# Zaliczeniowy.net
KiCad netlist of a schematic drawn in EAGLE
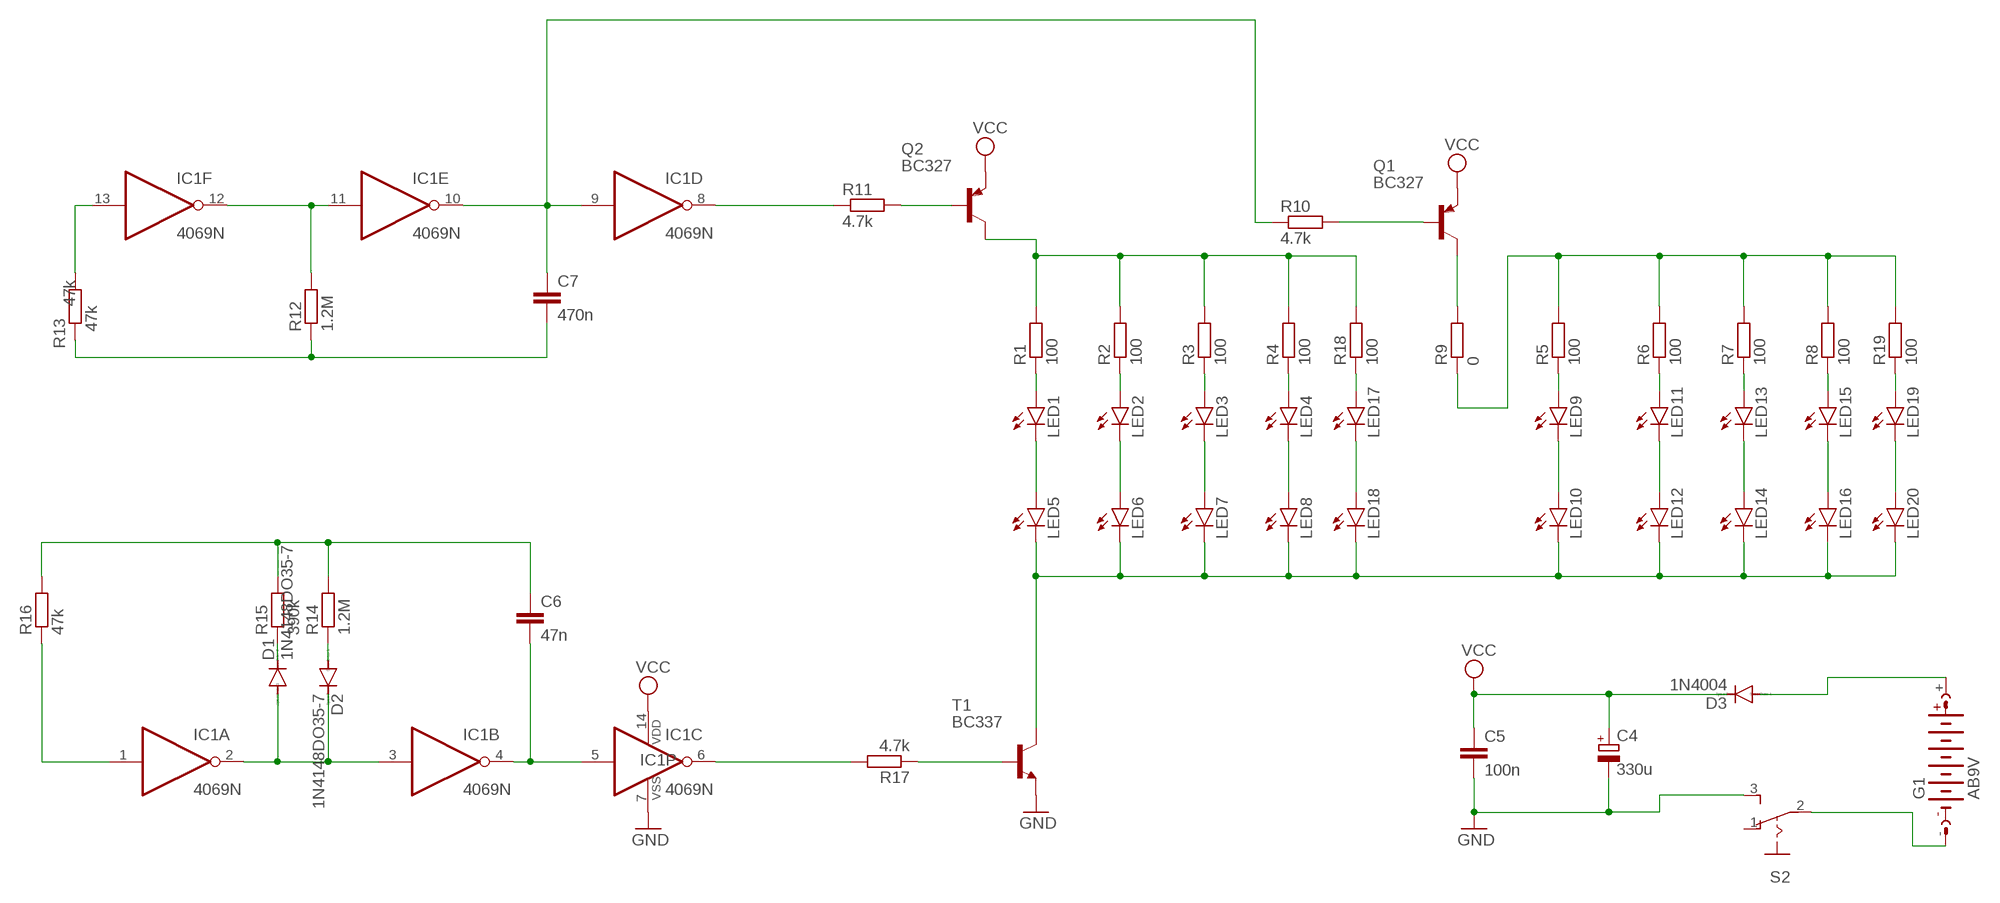
[diagram p0: schematic, sheet 1]

(export (version "E")
  (design (tool "Eeschema 10.0.6"))
  (components
    (comp (ref "C4")
      (value "330u")
      (footprint "eagle-import:E2-5")
      (libsource (lib "eagle-import") (part "CPOL-EUE2-5"))
    )
    (comp (ref "C5")
      (value "100n")
      (footprint "eagle-import:C025-024X044")
      (libsource (lib "eagle-import") (part "C-EU025-024X044"))
    )
    (comp (ref "C6")
      (value "47n")
      (footprint "eagle-import:C025-024X044")
      (libsource (lib "eagle-import") (part "C-EU025-024X044"))
    )
    (comp (ref "C7")
      (value "470n")
      (footprint "eagle-import:C025-024X044")
      (libsource (lib "eagle-import") (part "C-EU025-024X044"))
    )
    (comp (ref "D1")
      (value "1N4148DO35-7")
      (footprint "eagle-import:DO35-7")
      (libsource (lib "eagle-import") (part "1N4148DO35-7"))
    )
    (comp (ref "D2")
      (value "1N4148DO35-7")
      (footprint "eagle-import:DO35-7")
      (libsource (lib "eagle-import") (part "1N4148DO35-7"))
    )
    (comp (ref "D3")
      (value "1N4004")
      (footprint "eagle-import:DO41-10")
      (libsource (lib "eagle-import") (part "1N4004"))
    )
    (comp (ref "G1")
      (value "AB9V")
      (footprint "eagle-import:AB9V")
      (libsource (lib "eagle-import") (part "AB9V"))
    )
    (comp (ref "IC1")
      (value "4069N")
      (footprint "eagle-import:DIL14")
      (libsource (lib "eagle-import") (part "4069N"))
    )
    (comp (ref "LED1")
      (value "LED5MM")
      (footprint "eagle-import:LED5MM")
      (libsource (lib "eagle-import") (part "LED5MM"))
    )
    (comp (ref "LED2")
      (value "LED5MM")
      (footprint "eagle-import:LED5MM")
      (libsource (lib "eagle-import") (part "LED5MM"))
    )
    (comp (ref "LED3")
      (value "LED5MM")
      (footprint "eagle-import:LED5MM")
      (libsource (lib "eagle-import") (part "LED5MM"))
    )
    (comp (ref "LED4")
      (value "LED5MM")
      (footprint "eagle-import:LED5MM")
      (libsource (lib "eagle-import") (part "LED5MM"))
    )
    (comp (ref "LED5")
      (value "LED5MM")
      (footprint "eagle-import:LED5MM")
      (libsource (lib "eagle-import") (part "LED5MM"))
    )
    (comp (ref "LED6")
      (value "LED5MM")
      (footprint "eagle-import:LED5MM")
      (libsource (lib "eagle-import") (part "LED5MM"))
    )
    (comp (ref "LED7")
      (value "LED5MM")
      (footprint "eagle-import:LED5MM")
      (libsource (lib "eagle-import") (part "LED5MM"))
    )
    (comp (ref "LED8")
      (value "LED5MM")
      (footprint "eagle-import:LED5MM")
      (libsource (lib "eagle-import") (part "LED5MM"))
    )
    (comp (ref "LED9")
      (value "LED5MM")
      (footprint "eagle-import:LED5MM")
      (libsource (lib "eagle-import") (part "LED5MM"))
    )
    (comp (ref "LED10")
      (value "LED5MM")
      (footprint "eagle-import:LED5MM")
      (libsource (lib "eagle-import") (part "LED5MM"))
    )
    (comp (ref "LED11")
      (value "LED5MM")
      (footprint "eagle-import:LED5MM")
      (libsource (lib "eagle-import") (part "LED5MM"))
    )
    (comp (ref "LED12")
      (value "LED5MM")
      (footprint "eagle-import:LED5MM")
      (libsource (lib "eagle-import") (part "LED5MM"))
    )
    (comp (ref "LED13")
      (value "LED5MM")
      (footprint "eagle-import:LED5MM")
      (libsource (lib "eagle-import") (part "LED5MM"))
    )
    (comp (ref "LED14")
      (value "LED5MM")
      (footprint "eagle-import:LED5MM")
      (libsource (lib "eagle-import") (part "LED5MM"))
    )
    (comp (ref "LED15")
      (value "LED5MM")
      (footprint "eagle-import:LED5MM")
      (libsource (lib "eagle-import") (part "LED5MM"))
    )
    (comp (ref "LED16")
      (value "LED5MM")
      (footprint "eagle-import:LED5MM")
      (libsource (lib "eagle-import") (part "LED5MM"))
    )
    (comp (ref "LED17")
      (value "LED5MM")
      (footprint "eagle-import:LED5MM")
      (libsource (lib "eagle-import") (part "LED5MM"))
    )
    (comp (ref "LED18")
      (value "LED5MM")
      (footprint "eagle-import:LED5MM")
      (libsource (lib "eagle-import") (part "LED5MM"))
    )
    (comp (ref "LED19")
      (value "LED5MM")
      (footprint "eagle-import:LED5MM")
      (libsource (lib "eagle-import") (part "LED5MM"))
    )
    (comp (ref "LED20")
      (value "LED5MM")
      (footprint "eagle-import:LED5MM")
      (libsource (lib "eagle-import") (part "LED5MM"))
    )
    (comp (ref "Q1")
      (value "BC327")
      (footprint "eagle-import:TO92")
      (libsource (lib "eagle-import") (part "BC327"))
    )
    (comp (ref "Q2")
      (value "BC327")
      (footprint "eagle-import:TO92")
      (libsource (lib "eagle-import") (part "BC327"))
    )
    (comp (ref "R1")
      (value "100")
      (footprint "eagle-import:0207_7")
      (libsource (lib "eagle-import") (part "R-EU_0207/7"))
    )
    (comp (ref "R2")
      (value "100")
      (footprint "eagle-import:0207_7")
      (libsource (lib "eagle-import") (part "R-EU_0207/7"))
    )
    (comp (ref "R3")
      (value "100")
      (footprint "eagle-import:0207_7")
      (libsource (lib "eagle-import") (part "R-EU_0207/7"))
    )
    (comp (ref "R4")
      (value "100")
      (footprint "eagle-import:0207_7")
      (libsource (lib "eagle-import") (part "R-EU_0207/7"))
    )
    (comp (ref "R5")
      (value "100")
      (footprint "eagle-import:0207_7")
      (libsource (lib "eagle-import") (part "R-EU_0207/7"))
    )
    (comp (ref "R6")
      (value "100")
      (footprint "eagle-import:0207_7")
      (libsource (lib "eagle-import") (part "R-EU_0207/7"))
    )
    (comp (ref "R7")
      (value "100")
      (footprint "eagle-import:0207_7")
      (libsource (lib "eagle-import") (part "R-EU_0207/7"))
    )
    (comp (ref "R8")
      (value "100")
      (footprint "eagle-import:0207_7")
      (libsource (lib "eagle-import") (part "R-EU_0207/7"))
    )
    (comp (ref "R9")
      (value "0")
      (footprint "eagle-import:0207_7")
      (libsource (lib "eagle-import") (part "R-EU_0207/7"))
    )
    (comp (ref "R10")
      (value "4.7k")
      (footprint "eagle-import:0207_7")
      (libsource (lib "eagle-import") (part "R-EU_0207/7"))
    )
    (comp (ref "R11")
      (value "4.7k")
      (footprint "eagle-import:0207_7")
      (libsource (lib "eagle-import") (part "R-EU_0207/7"))
    )
    (comp (ref "R12")
      (value "1.2M")
      (footprint "eagle-import:0207_7")
      (libsource (lib "eagle-import") (part "R-EU_0207/7"))
    )
    (comp (ref "R13")
      (value "47k")
      (footprint "eagle-import:0207_7")
      (fields (field (name "POPULARITY") "46") (field (name "POPULARITY_1") "47k"))
      (libsource (lib "eagle-import") (part "R-EU_0207/7"))
    )
    (comp (ref "R14")
      (value "1.2M")
      (footprint "eagle-import:0207_7")
      (libsource (lib "eagle-import") (part "R-EU_0207/7"))
    )
    (comp (ref "R15")
      (value "390k")
      (footprint "eagle-import:0207_7")
      (libsource (lib "eagle-import") (part "R-EU_0207/7"))
    )
    (comp (ref "R16")
      (value "47k")
      (footprint "eagle-import:0207_7")
      (libsource (lib "eagle-import") (part "R-EU_0207/7"))
    )
    (comp (ref "R17")
      (value "4.7k")
      (footprint "eagle-import:0207_7")
      (libsource (lib "eagle-import") (part "R-EU_0207/7"))
    )
    (comp (ref "R18")
      (value "100")
      (footprint "eagle-import:0207_7")
      (libsource (lib "eagle-import") (part "R-EU_0207/7"))
    )
    (comp (ref "R19")
      (value "100")
      (footprint "eagle-import:0207_7")
      (libsource (lib "eagle-import") (part "R-EU_0207/7"))
    )
    (comp (ref "S2")
      (value "255SB")
      (footprint "eagle-import:255SB")
      (libsource (lib "eagle-import") (part "255SB"))
    )
    (comp (ref "T1")
      (value "BC337")
      (footprint "eagle-import:TO92-CBE")
      (libsource (lib "eagle-import") (part "-NPN-TO92-CBEBC337-16"))
    )
  )
  (nets
    (net (code "1") (name "GND") (class "Default")
      (node (ref "C4") (pin "-") (pinfunction "-_-") (pintype "passive"))
      (node (ref "C5") (pin "2") (pinfunction "2_2") (pintype "passive"))
      (node (ref "IC1") (pin "7") (pinfunction "VSS_7") (pintype "power_in"))
      (node (ref "S2") (pin "3") (pinfunction "S_3") (pintype "passive"))
      (node (ref "T1") (pin "E") (pinfunction "E_E") (pintype "passive"))
    )
    (net (code "2") (name "Net-(C6-Pad1)") (class "Default")
      (node (ref "C6") (pin "1") (pinfunction "1_1") (pintype "passive"))
      (node (ref "R14") (pin "2") (pinfunction "2_2") (pintype "passive"))
      (node (ref "R15") (pin "2") (pinfunction "2_2") (pintype "passive"))
      (node (ref "R16") (pin "2") (pinfunction "2_2") (pintype "passive"))
    )
    (net (code "3") (name "Net-(C7-Pad2)") (class "Default")
      (node (ref "C7") (pin "2") (pinfunction "2_2") (pintype "passive"))
      (node (ref "R12") (pin "1") (pinfunction "1_1") (pintype "passive"))
      (node (ref "R13") (pin "1") (pinfunction "1_1") (pintype "passive"))
    )
    (net (code "4") (name "Net-(D1-PadC)") (class "Default")
      (node (ref "D1") (pin "C") (pinfunction "C_C") (pintype "passive"))
      (node (ref "R15") (pin "1") (pinfunction "1_1") (pintype "passive"))
    )
    (net (code "5") (name "Net-(D2-PadA)") (class "Default")
      (node (ref "D2") (pin "A") (pinfunction "A_A") (pintype "passive"))
      (node (ref "R14") (pin "1") (pinfunction "1_1") (pintype "passive"))
    )
    (net (code "6") (name "Net-(D3-PadA)") (class "Default")
      (node (ref "D3") (pin "A") (pinfunction "A_A") (pintype "passive"))
      (node (ref "G1") (pin "+") (pinfunction "+_+") (pintype "passive"))
    )
    (net (code "7") (name "Net-(IC1A-I)") (class "Default")
      (node (ref "IC1") (pin "1") (pinfunction "I_1") (pintype "input"))
      (node (ref "R16") (pin "1") (pinfunction "1_1") (pintype "passive"))
    )
    (net (code "8") (name "Net-(IC1A-O)") (class "Default")
      (node (ref "D1") (pin "A") (pinfunction "A_A") (pintype "passive"))
      (node (ref "D2") (pin "C") (pinfunction "C_C") (pintype "passive"))
      (node (ref "IC1") (pin "2") (pinfunction "O_2") (pintype "output"))
      (node (ref "IC1") (pin "3") (pinfunction "I_3") (pintype "input"))
    )
    (net (code "9") (name "Net-(IC1B-O)") (class "Default")
      (node (ref "C6") (pin "2") (pinfunction "2_2") (pintype "passive"))
      (node (ref "IC1") (pin "4") (pinfunction "O_4") (pintype "output"))
      (node (ref "IC1") (pin "5") (pinfunction "I_5") (pintype "input"))
    )
    (net (code "10") (name "Net-(IC1C-O)") (class "Default")
      (node (ref "IC1") (pin "6") (pinfunction "O_6") (pintype "output"))
      (node (ref "R17") (pin "2") (pinfunction "2_2") (pintype "passive"))
    )
    (net (code "11") (name "Net-(IC1D-I)") (class "Default")
      (node (ref "C7") (pin "1") (pinfunction "1_1") (pintype "passive"))
      (node (ref "IC1") (pin "10") (pinfunction "O_10") (pintype "output"))
      (node (ref "IC1") (pin "9") (pinfunction "I_9") (pintype "input"))
      (node (ref "R10") (pin "1") (pinfunction "1_1") (pintype "passive"))
    )
    (net (code "12") (name "Net-(IC1D-O)") (class "Default")
      (node (ref "IC1") (pin "8") (pinfunction "O_8") (pintype "output"))
      (node (ref "R11") (pin "1") (pinfunction "1_1") (pintype "passive"))
    )
    (net (code "13") (name "Net-(IC1E-I)") (class "Default")
      (node (ref "IC1") (pin "11") (pinfunction "I_11") (pintype "input"))
      (node (ref "IC1") (pin "12") (pinfunction "O_12") (pintype "output"))
      (node (ref "R12") (pin "2") (pinfunction "2_2") (pintype "passive"))
    )
    (net (code "14") (name "Net-(IC1F-I)") (class "Default")
      (node (ref "IC1") (pin "13") (pinfunction "I_13") (pintype "input"))
      (node (ref "R13") (pin "2") (pinfunction "2_2") (pintype "passive"))
    )
    (net (code "15") (name "Net-(LED1-C)") (class "Default")
      (node (ref "LED1") (pin "K") (pinfunction "C_K") (pintype "passive"))
      (node (ref "LED5") (pin "A") (pinfunction "A_A") (pintype "passive"))
    )
    (net (code "16") (name "Net-(LED1-PadA)") (class "Default")
      (node (ref "LED1") (pin "A") (pinfunction "A_A") (pintype "passive"))
      (node (ref "R1") (pin "1") (pinfunction "1_1") (pintype "passive"))
    )
    (net (code "17") (name "Net-(LED2-C)") (class "Default")
      (node (ref "LED2") (pin "K") (pinfunction "C_K") (pintype "passive"))
      (node (ref "LED6") (pin "A") (pinfunction "A_A") (pintype "passive"))
    )
    (net (code "18") (name "Net-(LED2-PadA)") (class "Default")
      (node (ref "LED2") (pin "A") (pinfunction "A_A") (pintype "passive"))
      (node (ref "R2") (pin "1") (pinfunction "1_1") (pintype "passive"))
    )
    (net (code "19") (name "Net-(LED3-C)") (class "Default")
      (node (ref "LED3") (pin "K") (pinfunction "C_K") (pintype "passive"))
      (node (ref "LED7") (pin "A") (pinfunction "A_A") (pintype "passive"))
    )
    (net (code "20") (name "Net-(LED3-PadA)") (class "Default")
      (node (ref "LED3") (pin "A") (pinfunction "A_A") (pintype "passive"))
      (node (ref "R3") (pin "1") (pinfunction "1_1") (pintype "passive"))
    )
    (net (code "21") (name "Net-(LED4-C)") (class "Default")
      (node (ref "LED4") (pin "K") (pinfunction "C_K") (pintype "passive"))
      (node (ref "LED8") (pin "A") (pinfunction "A_A") (pintype "passive"))
    )
    (net (code "22") (name "Net-(LED4-PadA)") (class "Default")
      (node (ref "LED4") (pin "A") (pinfunction "A_A") (pintype "passive"))
      (node (ref "R4") (pin "1") (pinfunction "1_1") (pintype "passive"))
    )
    (net (code "23") (name "Net-(LED9-C)") (class "Default")
      (node (ref "LED10") (pin "A") (pinfunction "A_A") (pintype "passive"))
      (node (ref "LED9") (pin "K") (pinfunction "C_K") (pintype "passive"))
    )
    (net (code "24") (name "Net-(LED9-PadA)") (class "Default")
      (node (ref "LED9") (pin "A") (pinfunction "A_A") (pintype "passive"))
      (node (ref "R5") (pin "1") (pinfunction "1_1") (pintype "passive"))
    )
    (net (code "25") (name "Net-(LED10-C)") (class "Default")
      (node (ref "LED10") (pin "K") (pinfunction "C_K") (pintype "passive"))
      (node (ref "LED12") (pin "K") (pinfunction "C_K") (pintype "passive"))
      (node (ref "LED14") (pin "K") (pinfunction "C_K") (pintype "passive"))
      (node (ref "LED16") (pin "K") (pinfunction "C_K") (pintype "passive"))
      (node (ref "LED18") (pin "K") (pinfunction "C_K") (pintype "passive"))
      (node (ref "LED20") (pin "K") (pinfunction "C_K") (pintype "passive"))
      (node (ref "LED5") (pin "K") (pinfunction "C_K") (pintype "passive"))
      (node (ref "LED6") (pin "K") (pinfunction "C_K") (pintype "passive"))
      (node (ref "LED7") (pin "K") (pinfunction "C_K") (pintype "passive"))
      (node (ref "LED8") (pin "K") (pinfunction "C_K") (pintype "passive"))
      (node (ref "T1") (pin "C") (pinfunction "C_C") (pintype "passive"))
    )
    (net (code "26") (name "Net-(LED11-C)") (class "Default")
      (node (ref "LED11") (pin "K") (pinfunction "C_K") (pintype "passive"))
      (node (ref "LED12") (pin "A") (pinfunction "A_A") (pintype "passive"))
    )
    (net (code "27") (name "Net-(LED11-PadA)") (class "Default")
      (node (ref "LED11") (pin "A") (pinfunction "A_A") (pintype "passive"))
      (node (ref "R6") (pin "1") (pinfunction "1_1") (pintype "passive"))
    )
    (net (code "28") (name "Net-(LED13-C)") (class "Default")
      (node (ref "LED13") (pin "K") (pinfunction "C_K") (pintype "passive"))
      (node (ref "LED14") (pin "A") (pinfunction "A_A") (pintype "passive"))
    )
    (net (code "29") (name "Net-(LED13-PadA)") (class "Default")
      (node (ref "LED13") (pin "A") (pinfunction "A_A") (pintype "passive"))
      (node (ref "R7") (pin "1") (pinfunction "1_1") (pintype "passive"))
    )
    (net (code "30") (name "Net-(LED15-C)") (class "Default")
      (node (ref "LED15") (pin "K") (pinfunction "C_K") (pintype "passive"))
      (node (ref "LED16") (pin "A") (pinfunction "A_A") (pintype "passive"))
    )
    (net (code "31") (name "Net-(LED15-PadA)") (class "Default")
      (node (ref "LED15") (pin "A") (pinfunction "A_A") (pintype "passive"))
      (node (ref "R8") (pin "1") (pinfunction "1_1") (pintype "passive"))
    )
    (net (code "32") (name "Net-(LED17-C)") (class "Default")
      (node (ref "LED17") (pin "K") (pinfunction "C_K") (pintype "passive"))
      (node (ref "LED18") (pin "A") (pinfunction "A_A") (pintype "passive"))
    )
    (net (code "33") (name "Net-(LED17-PadA)") (class "Default")
      (node (ref "LED17") (pin "A") (pinfunction "A_A") (pintype "passive"))
      (node (ref "R18") (pin "1") (pinfunction "1_1") (pintype "passive"))
    )
    (net (code "34") (name "Net-(LED19-C)") (class "Default")
      (node (ref "LED19") (pin "K") (pinfunction "C_K") (pintype "passive"))
      (node (ref "LED20") (pin "A") (pinfunction "A_A") (pintype "passive"))
    )
    (net (code "35") (name "Net-(LED19-PadA)") (class "Default")
      (node (ref "LED19") (pin "A") (pinfunction "A_A") (pintype "passive"))
      (node (ref "R19") (pin "1") (pinfunction "1_1") (pintype "passive"))
    )
    (net (code "36") (name "Net-(Q1-B)") (class "Default")
      (node (ref "Q1") (pin "2") (pinfunction "B_2") (pintype "passive"))
      (node (ref "R10") (pin "2") (pinfunction "2_2") (pintype "passive"))
    )
    (net (code "37") (name "Net-(Q1-C)") (class "Default")
      (node (ref "Q1") (pin "3") (pinfunction "C_3") (pintype "passive"))
      (node (ref "R9") (pin "2") (pinfunction "2_2") (pintype "passive"))
    )
    (net (code "38") (name "Net-(Q2-B)") (class "Default")
      (node (ref "Q2") (pin "2") (pinfunction "B_2") (pintype "passive"))
      (node (ref "R11") (pin "2") (pinfunction "2_2") (pintype "passive"))
    )
    (net (code "39") (name "Net-(Q2-C)") (class "Default")
      (node (ref "Q2") (pin "3") (pinfunction "C_3") (pintype "passive"))
      (node (ref "R1") (pin "2") (pinfunction "2_2") (pintype "passive"))
      (node (ref "R18") (pin "2") (pinfunction "2_2") (pintype "passive"))
      (node (ref "R2") (pin "2") (pinfunction "2_2") (pintype "passive"))
      (node (ref "R3") (pin "2") (pinfunction "2_2") (pintype "passive"))
      (node (ref "R4") (pin "2") (pinfunction "2_2") (pintype "passive"))
    )
    (net (code "40") (name "Net-(R17-Pad1)") (class "Default")
      (node (ref "R17") (pin "1") (pinfunction "1_1") (pintype "passive"))
      (node (ref "T1") (pin "B") (pinfunction "B_B") (pintype "passive"))
    )
    (net (code "41") (name "Net-(R19-Pad2)") (class "Default")
      (node (ref "R19") (pin "2") (pinfunction "2_2") (pintype "passive"))
      (node (ref "R5") (pin "2") (pinfunction "2_2") (pintype "passive"))
      (node (ref "R6") (pin "2") (pinfunction "2_2") (pintype "passive"))
      (node (ref "R7") (pin "2") (pinfunction "2_2") (pintype "passive"))
      (node (ref "R8") (pin "2") (pinfunction "2_2") (pintype "passive"))
      (node (ref "R9") (pin "1") (pinfunction "1_1") (pintype "passive"))
    )
    (net (code "42") (name "Net-(S2-P)") (class "Default")
      (node (ref "G1") (pin "-") (pinfunction "-_-") (pintype "passive"))
      (node (ref "S2") (pin "2") (pinfunction "P_2") (pintype "passive"))
    )
    (net (code "43") (name "VCC") (class "Default")
      (node (ref "C4") (pin "+") (pinfunction "+_+") (pintype "passive"))
      (node (ref "C5") (pin "1") (pinfunction "1_1") (pintype "passive"))
      (node (ref "D3") (pin "C") (pinfunction "C_C") (pintype "passive"))
      (node (ref "IC1") (pin "14") (pinfunction "VDD_14") (pintype "power_in"))
      (node (ref "Q1") (pin "1") (pinfunction "E_1") (pintype "passive"))
      (node (ref "Q2") (pin "1") (pinfunction "E_1") (pintype "passive"))
    )
    (net (code "44") (name "unconnected-(S2-O-Pad1)") (class "Default")
      (node (ref "S2") (pin "1") (pinfunction "O_1") (pintype "passive"))
    )
  )
)
